# shinobi_BLE_connector.net
KiCad netlist of a schematic drawn in EAGLE
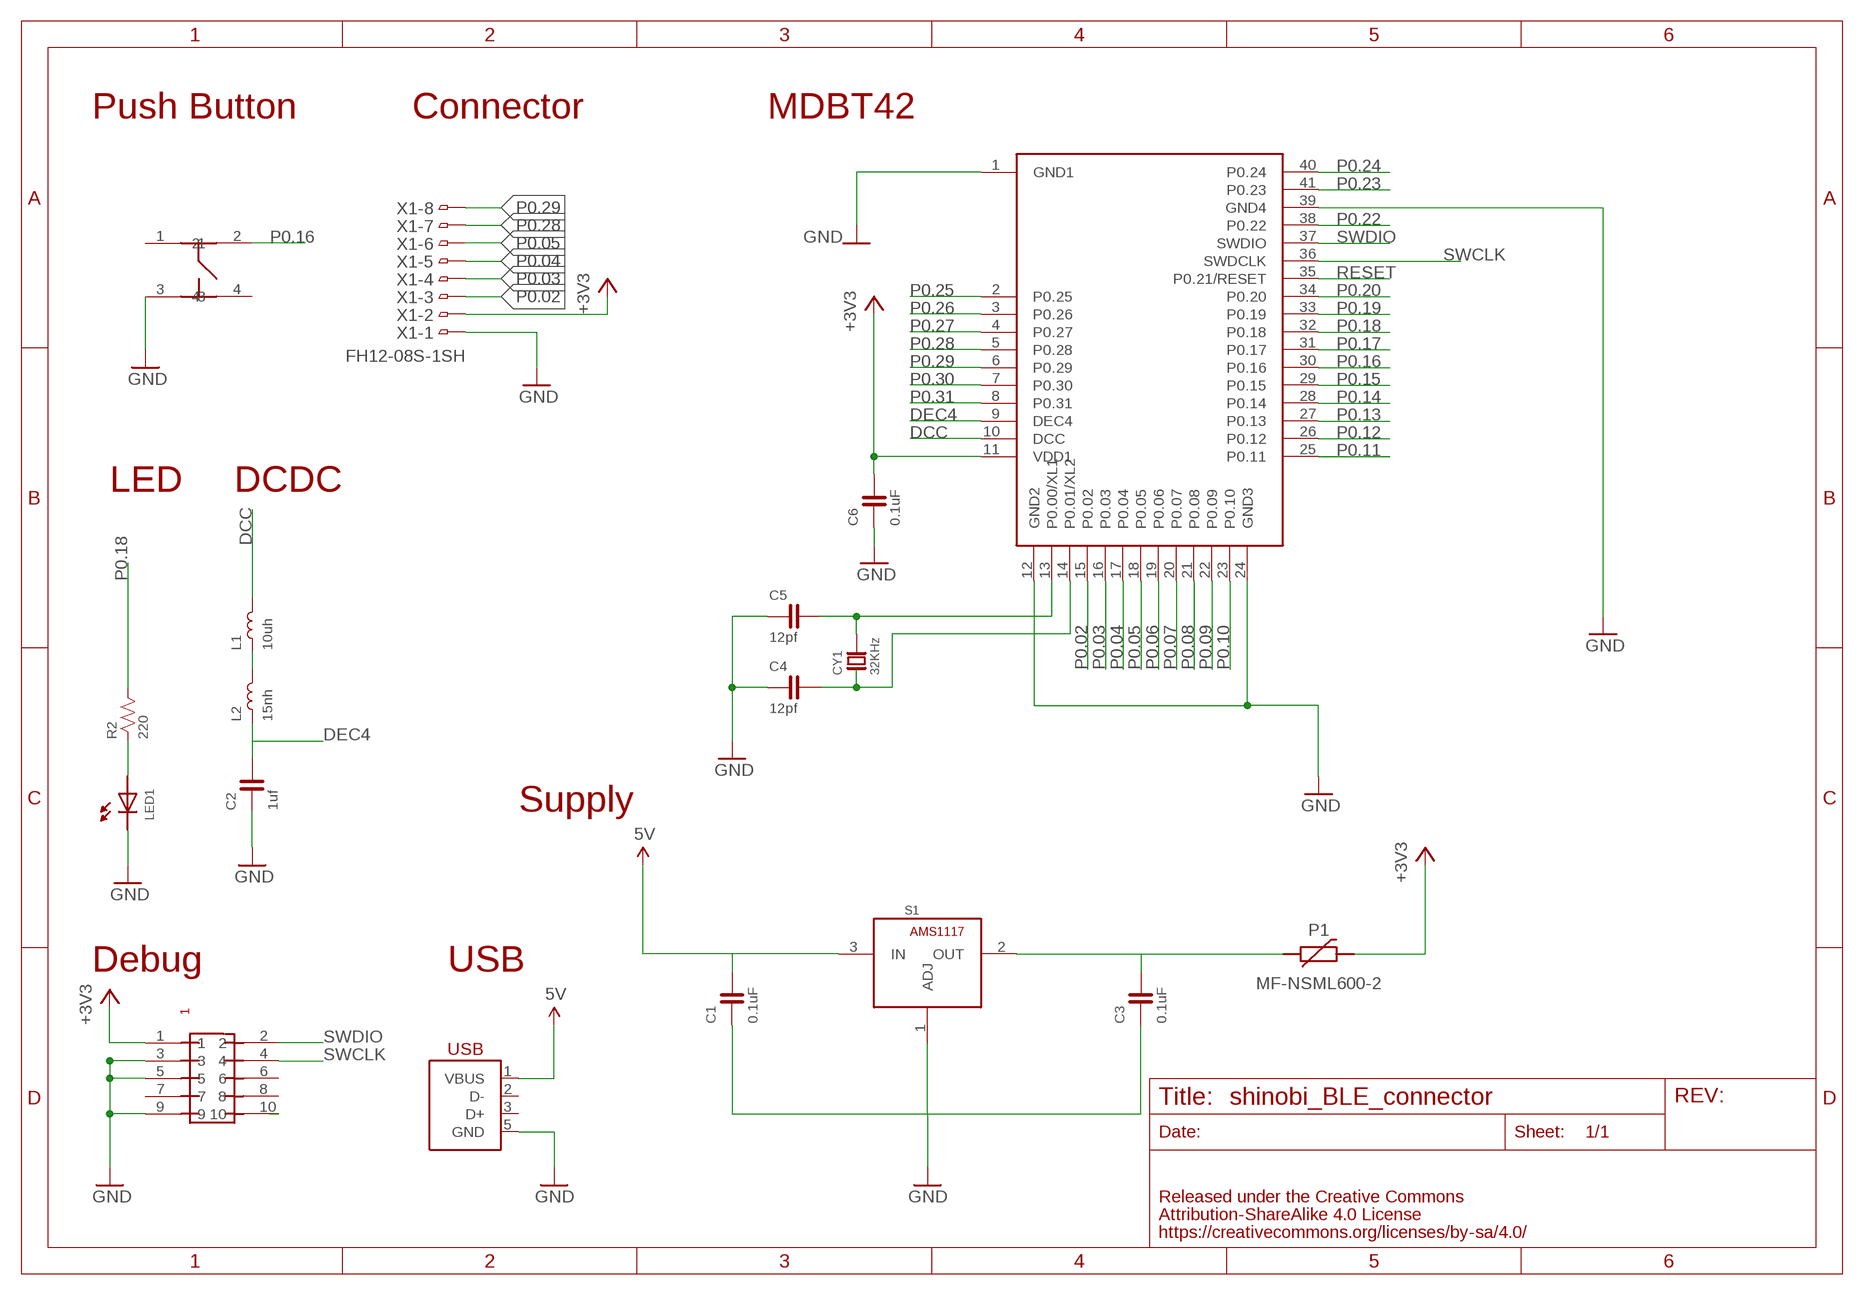
[diagram p0: schematic, sheet 1]

(export (version "E")
  (design (tool "Eeschema 10.0.6"))
  (components
    (comp (ref "C1")
      (value "0.1uF")
      (footprint "eagle-import:0603")
      (libsource (lib "eagle-import") (part "CAPACITOR-0603"))
    )
    (comp (ref "C2")
      (value "1uf")
      (footprint "eagle-import:0603")
      (libsource (lib "eagle-import") (part "CAPACITOR-0603"))
    )
    (comp (ref "C3")
      (value "0.1uF")
      (footprint "eagle-import:0603")
      (libsource (lib "eagle-import") (part "CAPACITOR-0603"))
    )
    (comp (ref "C4")
      (value "12pf")
      (footprint "eagle-import:0603")
      (libsource (lib "eagle-import") (part "CAPACITOR-0603"))
    )
    (comp (ref "C5")
      (value "12pf")
      (footprint "eagle-import:0603")
      (libsource (lib "eagle-import") (part "CAPACITOR-0603"))
    )
    (comp (ref "C6")
      (value "0.1uF")
      (footprint "eagle-import:0603")
      (libsource (lib "eagle-import") (part "CAPACITOR-0603"))
    )
    (comp (ref "CY1")
      (value "32KHz")
      (footprint "eagle-import:ABRACON-ABS07-32.768KHZ")
      (libsource (lib "eagle-import") (part "CRYSTAL-ABS07"))
    )
    (comp (ref "L1")
      (value "10uh")
      (footprint "eagle-import:0603")
      (libsource (lib "eagle-import") (part "INDUCTOR-0603"))
    )
    (comp (ref "L2")
      (value "15nh")
      (footprint "eagle-import:0603")
      (libsource (lib "eagle-import") (part "INDUCTOR-0603"))
    )
    (comp (ref "LED1")
      (value "LED-0603")
      (footprint "eagle-import:0603")
      (libsource (lib "eagle-import") (part "LED-0603"))
    )
    (comp (ref "P1")
      (value "MF-NSML600-2")
      (footprint "eagle-import:1206")
      (libsource (lib "eagle-import") (part "POLYSWITCH1206"))
    )
    (comp (ref "R2")
      (value "220")
      (footprint "eagle-import:0603")
      (libsource (lib "eagle-import") (part "RESISTOR-0603"))
    )
    (comp (ref "S1")
      (value "AMS1117")
      (footprint "eagle-import:SOT-223-3")
      (libsource (lib "eagle-import") (part "AMS1117"))
    )
    (comp (ref "U$2")
      (value "RAYTAC-MDBT42")
      (footprint "eagle-import:RAYTAC-MDBT42")
      (libsource (lib "eagle-import") (part "RAYTAC-MDBT42"))
    )
    (comp (ref "U$4")
      (value "PIN-HEADER-SMT(1.27MM)2X5")
      (footprint "eagle-import:PIN-HEADER-SMT(1.27MM)2X5")
      (libsource (lib "eagle-import") (part "PIN-HEADER-SMT(1.27MM)2X5"))
    )
    (comp (ref "U$5")
      (value "SWICTH-4P(KMR2)")
      (footprint "eagle-import:SWITCH-4P(KMR2)")
      (libsource (lib "eagle-import") (part "SWICTH-4P(KMR2)"))
    )
    (comp (ref "USB1")
      (value "USB-MICRO_B_SMT_HIROSE")
      (footprint "eagle-import:ZX62R-B-5P")
      (libsource (lib "eagle-import") (part "USB-MICRO_B_SMT_HIROSE"))
    )
    (comp (ref "X1")
      (value "FH12-08S-1SH")
      (footprint "eagle-import:FH12-08S-1SH")
      (libsource (lib "eagle-import") (part "FH12-08S-1SH"))
    )
  )
  (nets
    (net (code "1") (name "+3V3") (class "Default")
      (node (ref "C6") (pin "2") (pinfunction "2_2") (pintype "passive"))
      (node (ref "P1") (pin "P$2") (pinfunction "2_P$2") (pintype "bidirectional"))
      (node (ref "U$2") (pin "11") (pinfunction "VDD1_11") (pintype "bidirectional"))
      (node (ref "U$4") (pin "1") (pinfunction "1_1") (pintype "bidirectional"))
      (node (ref "X1") (pin "2") (pinfunction "1_2") (pintype "passive"))
    )
    (net (code "2") (name "/DCC") (class "Default")
      (node (ref "L1") (pin "2") (pinfunction "2_2") (pintype "bidirectional"))
      (node (ref "U$2") (pin "10") (pinfunction "DCC_10") (pintype "bidirectional"))
    )
    (net (code "3") (name "/DEC4") (class "Default")
      (node (ref "C2") (pin "2") (pinfunction "2_2") (pintype "passive"))
      (node (ref "L2") (pin "1") (pinfunction "1_1") (pintype "bidirectional"))
      (node (ref "U$2") (pin "9") (pinfunction "DEC4_9") (pintype "bidirectional"))
    )
    (net (code "4") (name "/P0.06") (class "Default")
      (node (ref "U$2") (pin "19") (pinfunction "P0.06_19") (pintype "bidirectional"))
    )
    (net (code "5") (name "/P0.07") (class "Default")
      (node (ref "U$2") (pin "20") (pinfunction "P0.07_20") (pintype "bidirectional"))
    )
    (net (code "6") (name "/P0.08") (class "Default")
      (node (ref "U$2") (pin "21") (pinfunction "P0.08_21") (pintype "bidirectional"))
    )
    (net (code "7") (name "/P0.09") (class "Default")
      (node (ref "U$2") (pin "22") (pinfunction "P0.09_22") (pintype "bidirectional"))
    )
    (net (code "8") (name "/P0.10") (class "Default")
      (node (ref "U$2") (pin "23") (pinfunction "P0.10_23") (pintype "bidirectional"))
    )
    (net (code "9") (name "/P0.11") (class "Default")
      (node (ref "U$2") (pin "25") (pinfunction "P0.11_25") (pintype "bidirectional"))
    )
    (net (code "10") (name "/P0.12") (class "Default")
      (node (ref "U$2") (pin "26") (pinfunction "P0.12_26") (pintype "bidirectional"))
    )
    (net (code "11") (name "/P0.13") (class "Default")
      (node (ref "U$2") (pin "27") (pinfunction "P0.13_27") (pintype "bidirectional"))
    )
    (net (code "12") (name "/P0.14") (class "Default")
      (node (ref "U$2") (pin "28") (pinfunction "P0.14_28") (pintype "bidirectional"))
    )
    (net (code "13") (name "/P0.15") (class "Default")
      (node (ref "U$2") (pin "29") (pinfunction "P0.15_29") (pintype "bidirectional"))
    )
    (net (code "14") (name "/P0.16") (class "Default")
      (node (ref "U$2") (pin "30") (pinfunction "P0.16_30") (pintype "bidirectional"))
      (node (ref "U$5") (pin "2") (pinfunction "2_2") (pintype "bidirectional"))
    )
    (net (code "15") (name "/P0.17") (class "Default")
      (node (ref "U$2") (pin "31") (pinfunction "P0.17_31") (pintype "bidirectional"))
    )
    (net (code "16") (name "/P0.18") (class "Default")
      (node (ref "R2") (pin "2") (pinfunction "2_2") (pintype "bidirectional"))
      (node (ref "U$2") (pin "32") (pinfunction "P0.18_32") (pintype "bidirectional"))
    )
    (net (code "17") (name "/P0.19") (class "Default")
      (node (ref "U$2") (pin "33") (pinfunction "P0.19_33") (pintype "bidirectional"))
    )
    (net (code "18") (name "/P0.20") (class "Default")
      (node (ref "U$2") (pin "34") (pinfunction "P0.20_34") (pintype "bidirectional"))
    )
    (net (code "19") (name "/P0.22") (class "Default")
      (node (ref "U$2") (pin "38") (pinfunction "P0.22_38") (pintype "bidirectional"))
    )
    (net (code "20") (name "/P0.23") (class "Default")
      (node (ref "U$2") (pin "41") (pinfunction "P0.23_41") (pintype "bidirectional"))
    )
    (net (code "21") (name "/P0.24") (class "Default")
      (node (ref "U$2") (pin "40") (pinfunction "P0.24_40") (pintype "bidirectional"))
    )
    (net (code "22") (name "/P0.25") (class "Default")
      (node (ref "U$2") (pin "2") (pinfunction "P0.25_2") (pintype "bidirectional"))
    )
    (net (code "23") (name "/P0.26") (class "Default")
      (node (ref "U$2") (pin "3") (pinfunction "P0.26_3") (pintype "bidirectional"))
    )
    (net (code "24") (name "/P0.27") (class "Default")
      (node (ref "U$2") (pin "4") (pinfunction "P0.27_4") (pintype "bidirectional"))
    )
    (net (code "25") (name "/P0.30") (class "Default")
      (node (ref "U$2") (pin "7") (pinfunction "P0.30_7") (pintype "bidirectional"))
    )
    (net (code "26") (name "/P0.31") (class "Default")
      (node (ref "U$2") (pin "8") (pinfunction "P0.31_8") (pintype "bidirectional"))
    )
    (net (code "27") (name "/RESET") (class "Default")
      (node (ref "U$2") (pin "35") (pinfunction "P0.21/RESET_35") (pintype "bidirectional"))
    )
    (net (code "28") (name "/SWCLK") (class "Default")
      (node (ref "U$2") (pin "36") (pinfunction "SWDCLK_36") (pintype "bidirectional"))
      (node (ref "U$4") (pin "4") (pinfunction "4_4") (pintype "bidirectional"))
    )
    (net (code "29") (name "/SWDIO") (class "Default")
      (node (ref "U$2") (pin "37") (pinfunction "SWDIO_37") (pintype "bidirectional"))
      (node (ref "U$4") (pin "2") (pinfunction "2_2") (pintype "bidirectional"))
    )
    (net (code "30") (name "5V") (class "Default")
      (node (ref "C1") (pin "2") (pinfunction "2_2") (pintype "passive"))
      (node (ref "S1") (pin "3") (pinfunction "IN_3") (pintype "bidirectional"))
      (node (ref "USB1") (pin "1") (pinfunction "VBUS_1") (pintype "bidirectional"))
    )
    (net (code "31") (name "GND") (class "Default")
      (node (ref "C1") (pin "1") (pinfunction "1_1") (pintype "passive"))
      (node (ref "C2") (pin "1") (pinfunction "1_1") (pintype "passive"))
      (node (ref "C3") (pin "1") (pinfunction "1_1") (pintype "passive"))
      (node (ref "C4") (pin "1") (pinfunction "1_1") (pintype "passive"))
      (node (ref "C5") (pin "1") (pinfunction "1_1") (pintype "passive"))
      (node (ref "C6") (pin "1") (pinfunction "1_1") (pintype "passive"))
      (node (ref "LED1") (pin "CATHODE") (pinfunction "CATHODE_CATHODE") (pintype "passive"))
      (node (ref "S1") (pin "1") (pinfunction "ADJ_1") (pintype "bidirectional"))
      (node (ref "U$2") (pin "1") (pinfunction "GND1_1") (pintype "bidirectional"))
      (node (ref "U$2") (pin "12") (pinfunction "GND2_12") (pintype "bidirectional"))
      (node (ref "U$2") (pin "24") (pinfunction "GND3_24") (pintype "bidirectional"))
      (node (ref "U$2") (pin "39") (pinfunction "GND4_39") (pintype "bidirectional"))
      (node (ref "U$4") (pin "3") (pinfunction "3_3") (pintype "bidirectional"))
      (node (ref "U$4") (pin "5") (pinfunction "5_5") (pintype "bidirectional"))
      (node (ref "U$4") (pin "9") (pinfunction "9_9") (pintype "bidirectional"))
      (node (ref "U$5") (pin "3") (pinfunction "3_3") (pintype "bidirectional"))
      (node (ref "USB1") (pin "5") (pinfunction "GND_5") (pintype "bidirectional"))
      (node (ref "X1") (pin "1") (pinfunction "1_1") (pintype "passive"))
    )
    (net (code "32") (name "Net-(L1-Pad1)") (class "Default")
      (node (ref "L1") (pin "1") (pinfunction "1_1") (pintype "bidirectional"))
      (node (ref "L2") (pin "2") (pinfunction "2_2") (pintype "bidirectional"))
    )
    (net (code "33") (name "Net-(LED1-PadANODE)") (class "Default")
      (node (ref "LED1") (pin "ANODE") (pinfunction "ANODE_ANODE") (pintype "passive"))
      (node (ref "R2") (pin "1") (pinfunction "1_1") (pintype "bidirectional"))
    )
    (net (code "34") (name "Net-(P1-1)") (class "Default")
      (node (ref "C3") (pin "2") (pinfunction "2_2") (pintype "passive"))
      (node (ref "P1") (pin "P$1") (pinfunction "1_P$1") (pintype "bidirectional"))
      (node (ref "S1") (pin "2") (pinfunction "OUT_2") (pintype "bidirectional"))
    )
    (net (code "35") (name "Net-(U$2-P0.00{slash}XL1)") (class "Default")
      (node (ref "C5") (pin "2") (pinfunction "2_2") (pintype "passive"))
      (node (ref "CY1") (pin "P$2") (pinfunction "P$2_P$2") (pintype "bidirectional"))
      (node (ref "U$2") (pin "13") (pinfunction "P0.00/XL1_13") (pintype "bidirectional"))
    )
    (net (code "36") (name "Net-(U$2-P0.01{slash}XL2)") (class "Default")
      (node (ref "C4") (pin "2") (pinfunction "2_2") (pintype "passive"))
      (node (ref "CY1") (pin "P$1") (pinfunction "P$1_P$1") (pintype "bidirectional"))
      (node (ref "U$2") (pin "14") (pinfunction "P0.01/XL2_14") (pintype "bidirectional"))
    )
    (net (code "37") (name "P0.02") (class "Default")
      (node (ref "U$2") (pin "15") (pinfunction "P0.02_15") (pintype "bidirectional"))
      (node (ref "X1") (pin "3") (pinfunction "1_3") (pintype "passive"))
    )
    (net (code "38") (name "P0.03") (class "Default")
      (node (ref "U$2") (pin "16") (pinfunction "P0.03_16") (pintype "bidirectional"))
      (node (ref "X1") (pin "4") (pinfunction "1_4") (pintype "passive"))
    )
    (net (code "39") (name "P0.04") (class "Default")
      (node (ref "U$2") (pin "17") (pinfunction "P0.04_17") (pintype "bidirectional"))
      (node (ref "X1") (pin "5") (pinfunction "1_5") (pintype "passive"))
    )
    (net (code "40") (name "P0.05") (class "Default")
      (node (ref "U$2") (pin "18") (pinfunction "P0.05_18") (pintype "bidirectional"))
      (node (ref "X1") (pin "6") (pinfunction "1_6") (pintype "passive"))
    )
    (net (code "41") (name "P0.28") (class "Default")
      (node (ref "U$2") (pin "5") (pinfunction "P0.28_5") (pintype "bidirectional"))
      (node (ref "X1") (pin "7") (pinfunction "1_7") (pintype "passive"))
    )
    (net (code "42") (name "P0.29") (class "Default")
      (node (ref "U$2") (pin "6") (pinfunction "P0.29_6") (pintype "bidirectional"))
      (node (ref "X1") (pin "8") (pinfunction "1_8") (pintype "passive"))
    )
    (net (code "43") (name "unconnected-(U$4-Pad6)") (class "Default")
      (node (ref "U$4") (pin "6") (pinfunction "6_6") (pintype "bidirectional"))
    )
    (net (code "44") (name "unconnected-(U$4-Pad7)") (class "Default")
      (node (ref "U$4") (pin "7") (pinfunction "7_7") (pintype "bidirectional"))
    )
    (net (code "45") (name "unconnected-(U$4-Pad8)") (class "Default")
      (node (ref "U$4") (pin "8") (pinfunction "8_8") (pintype "bidirectional"))
    )
    (net (code "46") (name "unconnected-(U$4-Pad10)") (class "Default")
      (node (ref "U$4") (pin "10") (pinfunction "10_10") (pintype "bidirectional"))
    )
    (net (code "47") (name "unconnected-(U$5-Pad1)") (class "Default")
      (node (ref "U$5") (pin "1") (pinfunction "1_1") (pintype "bidirectional"))
    )
    (net (code "48") (name "unconnected-(U$5-Pad4)") (class "Default")
      (node (ref "U$5") (pin "4") (pinfunction "4_4") (pintype "bidirectional"))
    )
    (net (code "49") (name "unconnected-(USB1-D+-Pad3)") (class "Default")
      (node (ref "USB1") (pin "3") (pinfunction "D+_3") (pintype "bidirectional"))
    )
    (net (code "50") (name "unconnected-(USB1-D--Pad2)") (class "Default")
      (node (ref "USB1") (pin "2") (pinfunction "D-_2") (pintype "bidirectional"))
    )
  )
)
